# wemos_weather_station.net
KiCad netlist of a schematic drawn in EAGLE
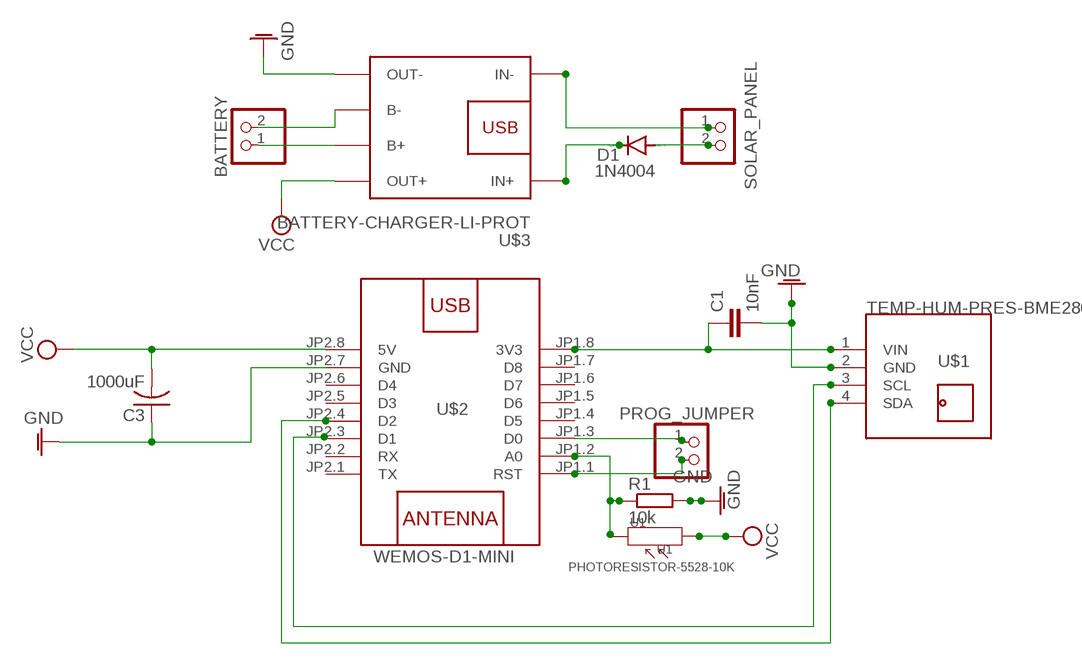
[diagram p0: schematic, sheet 1]

(export (version "E")
  (design (tool "Eeschema 10.0.6"))
  (components
    (comp (ref "BATTERY")
      (value "PINHD-1X2")
      (footprint "eagle-import:1X02")
      (libsource (lib "eagle-import") (part "PINHD-1X2"))
    )
    (comp (ref "C1")
      (value "10nF")
      (footprint "eagle-import:C025-025X050")
      (libsource (lib "eagle-import") (part "C-EU025-025X050"))
    )
    (comp (ref "C3")
      (value "1000uF")
      (footprint "eagle-import:C050-024X044")
      (libsource (lib "eagle-import") (part "C-US050-024X044"))
    )
    (comp (ref "D1")
      (value "1N4004")
      (footprint "eagle-import:DO41-10")
      (libsource (lib "eagle-import") (part "1N4004"))
    )
    (comp (ref "PROG_JUMPER")
      (value "PINHD-1X2")
      (footprint "eagle-import:1X02")
      (libsource (lib "eagle-import") (part "PINHD-1X2"))
    )
    (comp (ref "R1")
      (value "10k")
      (footprint "eagle-import:0204_7")
      (libsource (lib "eagle-import") (part "R-EU_0204/7"))
    )
    (comp (ref "SOLAR_PANEL")
      (value "PINHD-1X2")
      (footprint "eagle-import:1X02")
      (libsource (lib "eagle-import") (part "PINHD-1X2"))
    )
    (comp (ref "U$1")
      (value "TEMP-HUM-PRES-BME280")
      (footprint "eagle-import:TEMP-HUM-PRES-BME280")
      (libsource (lib "eagle-import") (part "TEMP-HUM-PRES-BME280"))
    )
    (comp (ref "U$2")
      (value "WEMOS-D1-MINI")
      (footprint "eagle-import:WEMOS-D1-MINI")
      (libsource (lib "eagle-import") (part "WEMOS-D1-MINI"))
    )
    (comp (ref "U$3")
      (value "BATTERY-CHARGER-LI-PROT")
      (footprint "eagle-import:BATTERY-CHARGER-LI-PROT")
      (libsource (lib "eagle-import") (part "BATTERY-CHARGER-LI-PROT"))
    )
    (comp (ref "U1")
      (value "PHOTORESISTOR-5528-10K")
      (footprint "eagle-import:SNR2-3.0")
      (libsource (lib "eagle-import") (part "PHOTORESISTOR-5528-10K(2P-5.0X4.2MM)"))
    )
  )
  (nets
    (net (code "1") (name "GND") (class "Default")
      (node (ref "C1") (pin "2") (pinfunction "2_2") (pintype "passive"))
      (node (ref "C3") (pin "1") (pinfunction "1_1") (pintype "passive"))
      (node (ref "R1") (pin "2") (pinfunction "2_2") (pintype "passive"))
      (node (ref "U$1") (pin "2") (pinfunction "GND_2") (pintype "power_in"))
      (node (ref "U$2") (pin "JP2.7") (pinfunction "GND_JP2.7") (pintype "power_in"))
      (node (ref "U$3") (pin "OUT-") (pinfunction "OUT-_OUT-") (pintype "bidirectional"))
    )
    (net (code "2") (name "Net-(BATTERY-Pad1)") (class "Default")
      (node (ref "BATTERY") (pin "1") (pinfunction "1_1") (pintype "passive"))
      (node (ref "U$3") (pin "B+") (pinfunction "B+_B+") (pintype "bidirectional"))
    )
    (net (code "3") (name "Net-(BATTERY-Pad2)") (class "Default")
      (node (ref "BATTERY") (pin "2") (pinfunction "2_2") (pintype "passive"))
      (node (ref "U$3") (pin "B-") (pinfunction "B-_B-") (pintype "bidirectional"))
    )
    (net (code "4") (name "Net-(D1-PadA)") (class "Default")
      (node (ref "D1") (pin "A") (pinfunction "A_A") (pintype "passive"))
      (node (ref "SOLAR_PANEL") (pin "2") (pinfunction "2_2") (pintype "passive"))
    )
    (net (code "5") (name "Net-(D1-PadC)") (class "Default")
      (node (ref "D1") (pin "C") (pinfunction "C_C") (pintype "passive"))
      (node (ref "U$3") (pin "IN+") (pinfunction "IN+_IN+") (pintype "bidirectional"))
    )
    (net (code "6") (name "Net-(SOLAR_PANEL-Pad1)") (class "Default")
      (node (ref "SOLAR_PANEL") (pin "1") (pinfunction "1_1") (pintype "passive"))
      (node (ref "U$3") (pin "IN-") (pinfunction "IN-_IN-") (pintype "bidirectional"))
    )
    (net (code "7") (name "Net-(U$1-SCL)") (class "Default")
      (node (ref "U$1") (pin "3") (pinfunction "SCL_3") (pintype "bidirectional"))
      (node (ref "U$2") (pin "JP2.3") (pinfunction "D1_JP2.3") (pintype "bidirectional"))
    )
    (net (code "8") (name "Net-(U$1-SDA)") (class "Default")
      (node (ref "U$1") (pin "4") (pinfunction "SDA_4") (pintype "bidirectional"))
      (node (ref "U$2") (pin "JP2.4") (pinfunction "D2_JP2.4") (pintype "bidirectional"))
    )
    (net (code "9") (name "Net-(U$1-VIN)") (class "Default")
      (node (ref "C1") (pin "1") (pinfunction "1_1") (pintype "passive"))
      (node (ref "U$1") (pin "1") (pinfunction "VIN_1") (pintype "power_in"))
      (node (ref "U$2") (pin "JP1.8") (pinfunction "3V3_JP1.8") (pintype "power_in"))
    )
    (net (code "10") (name "Net-(U$2-A0)") (class "Default")
      (node (ref "R1") (pin "1") (pinfunction "1_1") (pintype "passive"))
      (node (ref "U$2") (pin "JP1.2") (pinfunction "A0_JP1.2") (pintype "bidirectional"))
      (node (ref "U1") (pin "2") (pinfunction "P$2_2") (pintype "bidirectional"))
    )
    (net (code "11") (name "Net-(U$2-D0)") (class "Default")
      (node (ref "PROG_JUMPER") (pin "1") (pinfunction "1_1") (pintype "passive"))
      (node (ref "U$2") (pin "JP1.3") (pinfunction "D0_JP1.3") (pintype "bidirectional"))
    )
    (net (code "12") (name "Net-(U$2-RST)") (class "Default")
      (node (ref "PROG_JUMPER") (pin "2") (pinfunction "2_2") (pintype "passive"))
      (node (ref "U$2") (pin "JP1.1") (pinfunction "RST_JP1.1") (pintype "bidirectional"))
    )
    (net (code "13") (name "VCC") (class "Default")
      (node (ref "C3") (pin "2") (pinfunction "2_2") (pintype "passive"))
      (node (ref "U$2") (pin "JP2.8") (pinfunction "5V_JP2.8") (pintype "power_in"))
      (node (ref "U$3") (pin "OUT+") (pinfunction "OUT+_OUT+") (pintype "bidirectional"))
      (node (ref "U1") (pin "1") (pinfunction "P$1_1") (pintype "bidirectional"))
    )
    (net (code "14") (name "unconnected-(U$2-D3-PadJP2.5)") (class "Default")
      (node (ref "U$2") (pin "JP2.5") (pinfunction "D3_JP2.5") (pintype "bidirectional"))
    )
    (net (code "15") (name "unconnected-(U$2-D4-PadJP2.6)") (class "Default")
      (node (ref "U$2") (pin "JP2.6") (pinfunction "D4_JP2.6") (pintype "bidirectional"))
    )
    (net (code "16") (name "unconnected-(U$2-D5-PadJP1.4)") (class "Default")
      (node (ref "U$2") (pin "JP1.4") (pinfunction "D5_JP1.4") (pintype "bidirectional"))
    )
    (net (code "17") (name "unconnected-(U$2-D6-PadJP1.5)") (class "Default")
      (node (ref "U$2") (pin "JP1.5") (pinfunction "D6_JP1.5") (pintype "bidirectional"))
    )
    (net (code "18") (name "unconnected-(U$2-D7-PadJP1.6)") (class "Default")
      (node (ref "U$2") (pin "JP1.6") (pinfunction "D7_JP1.6") (pintype "bidirectional"))
    )
    (net (code "19") (name "unconnected-(U$2-D8-PadJP1.7)") (class "Default")
      (node (ref "U$2") (pin "JP1.7") (pinfunction "D8_JP1.7") (pintype "bidirectional"))
    )
    (net (code "20") (name "unconnected-(U$2-RX-PadJP2.2)") (class "Default")
      (node (ref "U$2") (pin "JP2.2") (pinfunction "RX_JP2.2") (pintype "bidirectional"))
    )
    (net (code "21") (name "unconnected-(U$2-TX-PadJP2.1)") (class "Default")
      (node (ref "U$2") (pin "JP2.1") (pinfunction "TX_JP2.1") (pintype "bidirectional"))
    )
  )
)
